# Power.net
KiCad netlist of a schematic drawn in Altium Designer
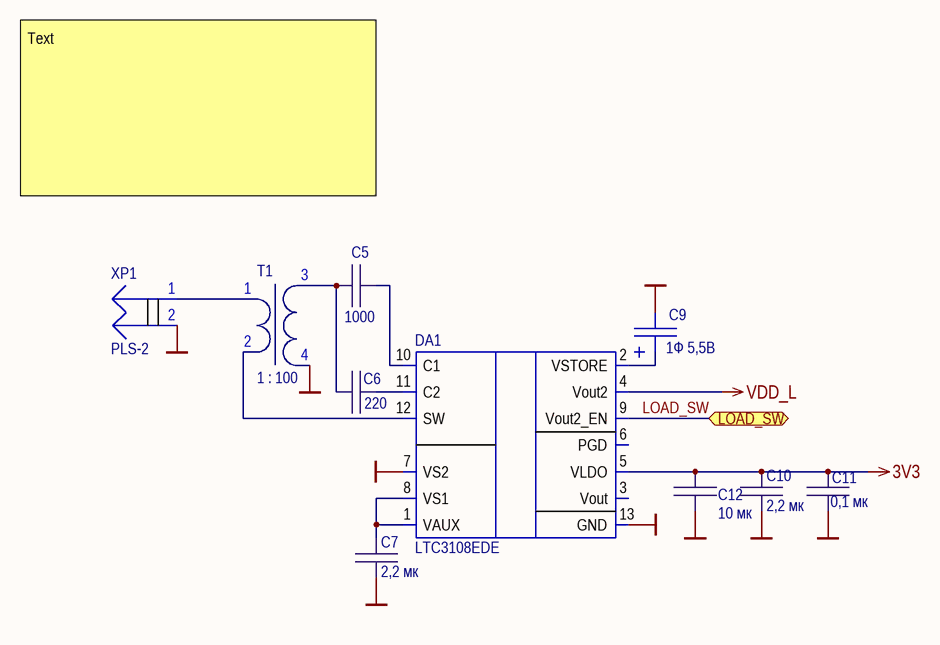
[diagram p0: Power.SchDoc]

(export (version "E")
  (design (tool "Eeschema 10.0.6"))
  (components
    (comp (ref "C5")
      (value "1000")
      (footprint "C_0603")
      (description "CAP CER 1000PF 50V C0G/NP0 0603")
      (fields
        (field (name "PART NUMBER") "GRM1885C1H102FA01J")
        (field (name "MANUFACTURER") "Murata Electronics")
      )
      (libsource (lib "Database_Lib") (part "Capasitor"))
    )
    (comp (ref "C6")
      (value "220")
      (footprint "C_0603")
      (description "CAP CER 220PF 100V C0G/NP0 0603")
      (fields
        (field (name "PART NUMBER") "GRM1885C2A221FA01D")
        (field (name "MANUFACTURER") "Murata Electronics")
      )
      (libsource (lib "Database_Lib") (part "Capasitor"))
    )
    (comp (ref "C7")
      (value "2,2 мк")
      (footprint "C_0603")
      (description "CAP CER 2.2UF 25V X5R 0603")
      (fields
        (field (name "PART NUMBER") "GRM188R61E225MA12D")
        (field (name "MANUFACTURER") "Murata Electronics")
      )
      (libsource (lib "Database_Lib") (part "Capasitor"))
    )
    (comp (ref "C9")
      (value "1Ф 5,5В")
      (footprint "EECF5R5u")
      (description "1 Ф, 5.5 В, 5 мм, 2208H, Ионистор")
      (libsource (lib "2.Capasitors") (part "EECF5R5U105"))
    )
    (comp (ref "C10")
      (value "2,2 мк")
      (footprint "C_0603")
      (description "CAP CER 2.2UF 25V X5R 0603")
      (fields
        (field (name "PART NUMBER") "GRM188R61E225MA12D")
        (field (name "MANUFACTURER") "Murata Electronics")
      )
      (libsource (lib "Database_Lib") (part "Capasitor"))
    )
    (comp (ref "C11")
      (value "0,1 мк")
      (footprint "C_0603")
      (description "CAP CER 0.1UF 100V X7R 0603")
      (fields
        (field (name "PART NUMBER") "GRM188R72A104MA35D")
        (field (name "MANUFACTURER") "Murata Electronics")
      )
      (libsource (lib "Database_Lib") (part "Capasitor"))
    )
    (comp (ref "C12")
      (value "10 мк")
      (footprint "C_0603")
      (description "CAP CER 10UF 6.3V X5R 0603")
      (fields
        (field (name "PART NUMBER") "GRM185R60J106ME15J")
        (field (name "MANUFACTURER") "Murata Electronics")
      )
      (libsource (lib "Database_Lib") (part "Capasitor"))
    )
    (comp (ref "DA1")
      (value "LTC3108EDE")
      (footprint "DFN-12")
      (description "Ultralow Voltage Step-Up Converter and Power Manager")
      (libsource (lib "6.Chips") (part "LTC3108EDE"))
    )
    (comp (ref "T1")
      (value "1 : 100")
      (footprint "LPR6235")
      (description "Coupled Inductor")
      (libsource (lib "13.Transformers") (part "LPR6235-752SMR"))
    )
    (comp (ref "XP1") (value "PLS-2") (footprint "PLS-2") (libsource (lib "7.Connectors") (part "PLS-2")))
  )
  (nets
    (net (code "1") (name "/LOAD_SW") (class "Default")
      (node (ref "DA1") (pin "9") (pinfunction "Vout2_EN_9") (pintype "passive"))
    )
    (net (code "2") (name "3V3") (class "Default")
      (node (ref "C10") (pin "2") (pinfunction "2_2") (pintype "passive"))
      (node (ref "C11") (pin "2") (pinfunction "2_2") (pintype "passive"))
      (node (ref "C12") (pin "2") (pinfunction "2_2") (pintype "passive"))
      (node (ref "DA1") (pin "5") (pinfunction "VLDO_5") (pintype "passive"))
    )
    (net (code "3") (name "GND") (class "Default")
      (node (ref "C10") (pin "1") (pinfunction "1_1") (pintype "passive"))
      (node (ref "C11") (pin "1") (pinfunction "1_1") (pintype "passive"))
      (node (ref "C12") (pin "1") (pinfunction "1_1") (pintype "passive"))
      (node (ref "C7") (pin "1") (pinfunction "1_1") (pintype "passive"))
      (node (ref "C9") (pin "2") (pinfunction "2_2") (pintype "passive"))
      (node (ref "DA1") (pin "13") (pinfunction "GND_13") (pintype "passive"))
      (node (ref "DA1") (pin "7") (pinfunction "VS2_7") (pintype "passive"))
      (node (ref "T1") (pin "4") (pinfunction "4_4") (pintype "passive"))
      (node (ref "XP1") (pin "2") (pinfunction "2_2") (pintype "passive"))
    )
    (net (code "4") (name "Net-(C5-Pad1)") (class "Default")
      (node (ref "C5") (pin "1") (pinfunction "1_1") (pintype "passive"))
      (node (ref "C6") (pin "1") (pinfunction "1_1") (pintype "passive"))
      (node (ref "T1") (pin "3") (pinfunction "3_3") (pintype "passive"))
    )
    (net (code "5") (name "Net-(DA1-C1)") (class "Default")
      (node (ref "C5") (pin "2") (pinfunction "2_2") (pintype "passive"))
      (node (ref "DA1") (pin "10") (pinfunction "C1_10") (pintype "passive"))
    )
    (net (code "6") (name "Net-(DA1-C2)") (class "Default")
      (node (ref "C6") (pin "2") (pinfunction "2_2") (pintype "passive"))
      (node (ref "DA1") (pin "11") (pinfunction "C2_11") (pintype "passive"))
    )
    (net (code "7") (name "Net-(DA1-SW)") (class "Default")
      (node (ref "DA1") (pin "12") (pinfunction "SW_12") (pintype "passive"))
      (node (ref "T1") (pin "2") (pinfunction "2_2") (pintype "passive"))
    )
    (net (code "8") (name "Net-(DA1-VAUX)") (class "Default")
      (node (ref "C7") (pin "2") (pinfunction "2_2") (pintype "passive"))
      (node (ref "DA1") (pin "1") (pinfunction "VAUX_1") (pintype "passive"))
      (node (ref "DA1") (pin "8") (pinfunction "VS1_8") (pintype "passive"))
    )
    (net (code "9") (name "Net-(DA1-VSTORE)") (class "Default")
      (node (ref "C9") (pin "1") (pinfunction "1_1") (pintype "passive"))
      (node (ref "DA1") (pin "2") (pinfunction "VSTORE_2") (pintype "passive"))
    )
    (net (code "10") (name "Net-(T1-Pad1)") (class "Default")
      (node (ref "T1") (pin "1") (pinfunction "1_1") (pintype "passive"))
      (node (ref "XP1") (pin "1") (pinfunction "1_1") (pintype "passive"))
    )
    (net (code "11") (name "VDD_L") (class "Default")
      (node (ref "DA1") (pin "4") (pinfunction "Vout2_4") (pintype "passive"))
    )
    (net (code "12") (name "unconnected-(DA1-PGD-Pad6)") (class "Default")
      (node (ref "DA1") (pin "6") (pinfunction "PGD_6") (pintype "passive"))
    )
    (net (code "13") (name "unconnected-(DA1-Vout-Pad3)") (class "Default")
      (node (ref "DA1") (pin "3") (pinfunction "Vout_3") (pintype "passive"))
    )
  )
)
